# Arduino_Uno_Satyajeet.net
KiCad netlist of a schematic drawn in EAGLE
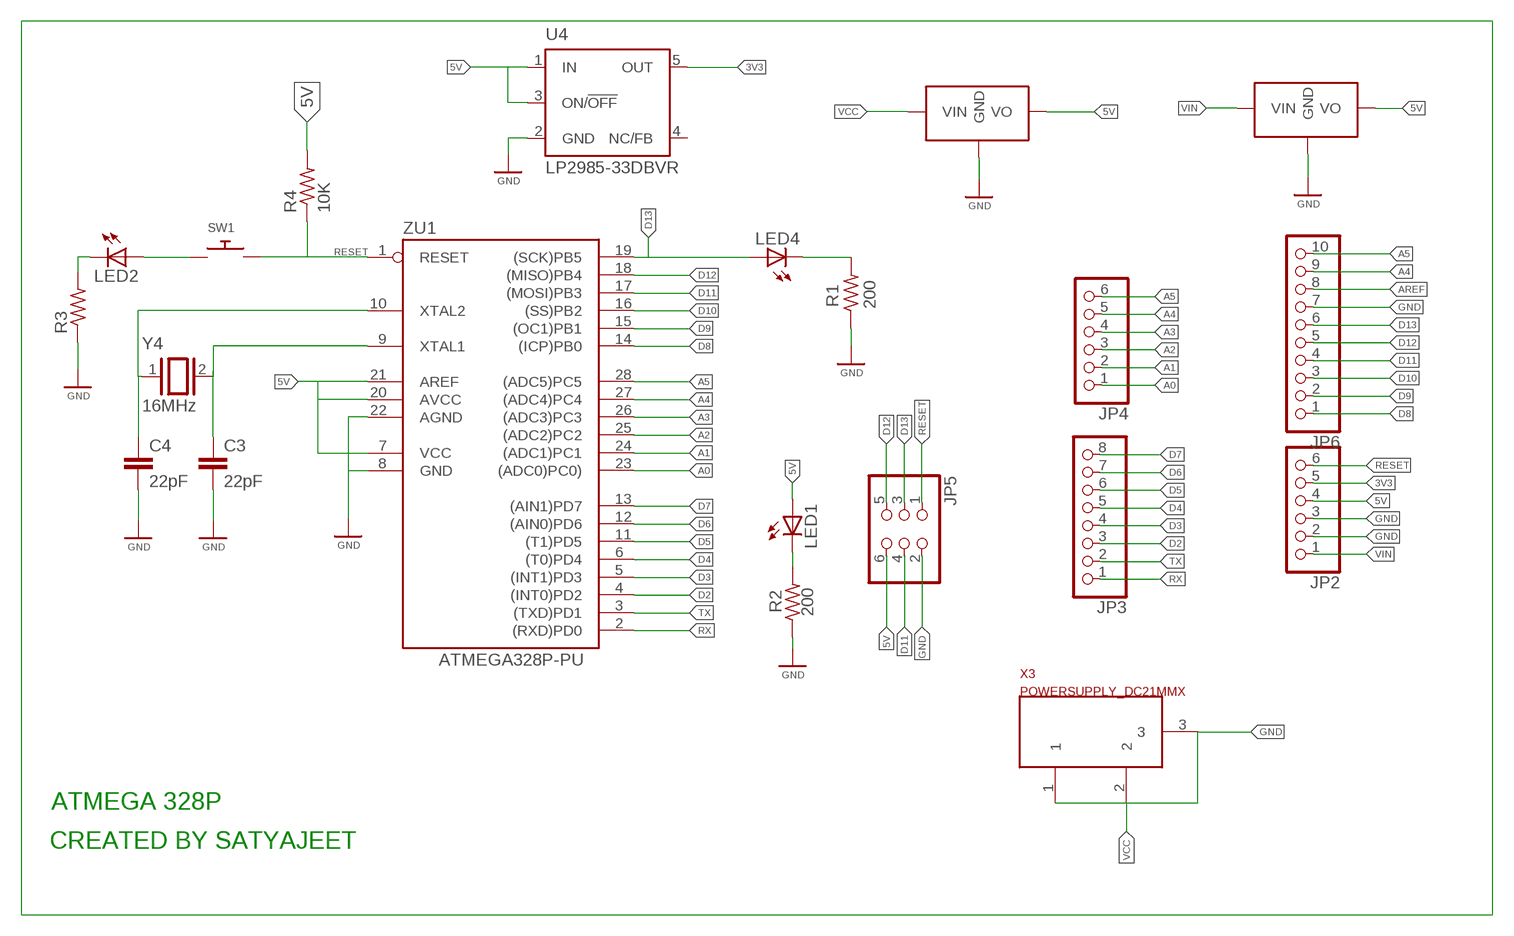
[diagram p0: schematic, sheet 1]

(export (version "E")
  (design (tool "Eeschema 10.0.6"))
  (components
    (comp (ref "C3")
      (value "22pF")
      (footprint "eagle-import:C2.5-2")
      (libsource (lib "eagle-import") (part "C2.5/2"))
    )
    (comp (ref "C4")
      (value "22pF")
      (footprint "eagle-import:C2.5-2")
      (libsource (lib "eagle-import") (part "C2.5/2"))
    )
    (comp (ref "JP2")
      (value "PINHD-1X6")
      (footprint "eagle-import:1X06")
      (libsource (lib "eagle-import") (part "PINHD-1X6"))
    )
    (comp (ref "JP3")
      (value "PINHD-1X8")
      (footprint "eagle-import:1X08")
      (libsource (lib "eagle-import") (part "PINHD-1X8"))
    )
    (comp (ref "JP4")
      (value "PINHD-1X6")
      (footprint "eagle-import:1X06")
      (libsource (lib "eagle-import") (part "PINHD-1X6"))
    )
    (comp (ref "JP5")
      (value "PINHD-2X3")
      (footprint "eagle-import:2X03")
      (libsource (lib "eagle-import") (part "PINHD-2X3"))
    )
    (comp (ref "JP6")
      (value "PINHD-1X10")
      (footprint "eagle-import:1X10")
      (libsource (lib "eagle-import") (part "PINHD-1X10"))
    )
    (comp (ref "LED1")
      (value "LED5MM")
      (footprint "eagle-import:LED5MM")
      (libsource (lib "eagle-import") (part "LED5MM"))
    )
    (comp (ref "LED2")
      (value "LED5MM")
      (footprint "eagle-import:LED5MM")
      (libsource (lib "eagle-import") (part "LED5MM"))
    )
    (comp (ref "LED4")
      (value "LED5MM")
      (footprint "eagle-import:LED5MM")
      (libsource (lib "eagle-import") (part "LED5MM"))
    )
    (comp (ref "R1")
      (value "200")
      (footprint "eagle-import:0204_5")
      (libsource (lib "eagle-import") (part "R-US_0204/5"))
    )
    (comp (ref "R2")
      (value "200")
      (footprint "eagle-import:0204_5")
      (libsource (lib "eagle-import") (part "R-US_0204/5"))
    )
    (comp (ref "R3")
      (value "R-US_0204/5")
      (footprint "eagle-import:0204_5")
      (libsource (lib "eagle-import") (part "R-US_0204/5"))
    )
    (comp (ref "R4")
      (value "10K")
      (footprint "eagle-import:0204_5")
      (libsource (lib "eagle-import") (part "R-US_0204/5"))
    )
    (comp (ref "SW1")
      (value "SWITCH_PUSHBUTTONEVQ-PE")
      (footprint "eagle-import:TACT_PANA-EVQ")
      (libsource (lib "eagle-import") (part "SWITCH_PUSHBUTTONEVQ-PE"))
    )
    (comp (ref "U$1")
      (value "AB_7805_FLAT")
      (footprint "eagle-import:AB_7805_FLAT")
      (libsource (lib "eagle-import") (part "AB_7805_FLAT"))
    )
    (comp (ref "U$2")
      (value "AB_7805_FLAT")
      (footprint "eagle-import:AB_7805_FLAT")
      (libsource (lib "eagle-import") (part "AB_7805_FLAT"))
    )
    (comp (ref "U4")
      (value "LP2985-33DBVR")
      (footprint "eagle-import:SOT23-DBV")
      (libsource (lib "eagle-import") (part "LP2985-XXDBVR33"))
    )
    (comp (ref "X3")
      (value "POWERSUPPLY_DC21MMX")
      (footprint "eagle-import:POWERSUPPLY_DC-21MM")
      (libsource (lib "eagle-import") (part "POWERSUPPLY_DC21MMX"))
    )
    (comp (ref "Y4")
      (value "16MHz")
      (footprint "eagle-import:QS")
      (libsource (lib "eagle-import") (part "XTAL/S"))
    )
    (comp (ref "ZU1")
      (value "ATMEGA328P-PU")
      (footprint "eagle-import:DIL28-3")
      (libsource (lib "eagle-import") (part "ATMEGA328P-PU"))
    )
  )
  (nets
    (net (code "1") (name "3V3") (class "Default")
      (node (ref "JP2") (pin "5") (pinfunction "5_5") (pintype "passive"))
      (node (ref "U4") (pin "5") (pinfunction "OUT_5") (pintype "passive"))
    )
    (net (code "2") (name "5V") (class "Default")
      (node (ref "JP2") (pin "4") (pinfunction "4_4") (pintype "passive"))
      (node (ref "JP5") (pin "6") (pinfunction "6_6") (pintype "passive"))
      (node (ref "LED1") (pin "A") (pinfunction "A_A") (pintype "passive"))
      (node (ref "R4") (pin "2") (pinfunction "2_2") (pintype "passive"))
      (node (ref "U$1") (pin "3") (pinfunction "VO_3") (pintype "bidirectional"))
      (node (ref "U$2") (pin "3") (pinfunction "VO_3") (pintype "bidirectional"))
      (node (ref "U4") (pin "1") (pinfunction "IN_1") (pintype "input"))
      (node (ref "ZU1") (pin "21") (pinfunction "AREF_21") (pintype "passive"))
    )
    (net (code "3") (name "A0") (class "Default")
      (node (ref "JP4") (pin "1") (pinfunction "1_1") (pintype "passive"))
      (node (ref "ZU1") (pin "23") (pinfunction "(ADC0)PC0)_23") (pintype "bidirectional"))
    )
    (net (code "4") (name "A1") (class "Default")
      (node (ref "JP4") (pin "2") (pinfunction "2_2") (pintype "passive"))
      (node (ref "ZU1") (pin "24") (pinfunction "(ADC1)PC1_24") (pintype "bidirectional"))
    )
    (net (code "5") (name "A2") (class "Default")
      (node (ref "JP4") (pin "3") (pinfunction "3_3") (pintype "passive"))
      (node (ref "ZU1") (pin "25") (pinfunction "(ADC2)PC2_25") (pintype "bidirectional"))
    )
    (net (code "6") (name "A3") (class "Default")
      (node (ref "JP4") (pin "4") (pinfunction "4_4") (pintype "passive"))
      (node (ref "ZU1") (pin "26") (pinfunction "(ADC3)PC3_26") (pintype "bidirectional"))
    )
    (net (code "7") (name "A4") (class "Default")
      (node (ref "JP4") (pin "5") (pinfunction "5_5") (pintype "passive"))
      (node (ref "JP6") (pin "9") (pinfunction "9_9") (pintype "passive"))
      (node (ref "ZU1") (pin "27") (pinfunction "(ADC4)PC4_27") (pintype "bidirectional"))
    )
    (net (code "8") (name "A5") (class "Default")
      (node (ref "JP4") (pin "6") (pinfunction "6_6") (pintype "passive"))
      (node (ref "JP6") (pin "10") (pinfunction "10_10") (pintype "passive"))
      (node (ref "ZU1") (pin "28") (pinfunction "(ADC5)PC5_28") (pintype "bidirectional"))
    )
    (net (code "9") (name "AREF") (class "Default")
      (node (ref "JP6") (pin "8") (pinfunction "8_8") (pintype "passive"))
    )
    (net (code "10") (name "D2") (class "Default")
      (node (ref "JP3") (pin "3") (pinfunction "3_3") (pintype "passive"))
      (node (ref "ZU1") (pin "4") (pinfunction "(INT0)PD2_4") (pintype "bidirectional"))
    )
    (net (code "11") (name "D3") (class "Default")
      (node (ref "JP3") (pin "4") (pinfunction "4_4") (pintype "passive"))
      (node (ref "ZU1") (pin "5") (pinfunction "(INT1)PD3_5") (pintype "bidirectional"))
    )
    (net (code "12") (name "D4") (class "Default")
      (node (ref "JP3") (pin "5") (pinfunction "5_5") (pintype "passive"))
      (node (ref "ZU1") (pin "6") (pinfunction "(T0)PD4_6") (pintype "bidirectional"))
    )
    (net (code "13") (name "D5") (class "Default")
      (node (ref "JP3") (pin "6") (pinfunction "6_6") (pintype "passive"))
      (node (ref "ZU1") (pin "11") (pinfunction "(T1)PD5_11") (pintype "bidirectional"))
    )
    (net (code "14") (name "D6") (class "Default")
      (node (ref "JP3") (pin "7") (pinfunction "7_7") (pintype "passive"))
      (node (ref "ZU1") (pin "12") (pinfunction "(AIN0)PD6_12") (pintype "bidirectional"))
    )
    (net (code "15") (name "D7") (class "Default")
      (node (ref "JP3") (pin "8") (pinfunction "8_8") (pintype "passive"))
      (node (ref "ZU1") (pin "13") (pinfunction "(AIN1)PD7_13") (pintype "bidirectional"))
    )
    (net (code "16") (name "D8") (class "Default")
      (node (ref "JP6") (pin "1") (pinfunction "1_1") (pintype "passive"))
      (node (ref "ZU1") (pin "14") (pinfunction "(ICP)PB0_14") (pintype "bidirectional"))
    )
    (net (code "17") (name "D9") (class "Default")
      (node (ref "JP6") (pin "2") (pinfunction "2_2") (pintype "passive"))
      (node (ref "ZU1") (pin "15") (pinfunction "(OC1)PB1_15") (pintype "bidirectional"))
    )
    (net (code "18") (name "D10") (class "Default")
      (node (ref "JP6") (pin "3") (pinfunction "3_3") (pintype "passive"))
      (node (ref "ZU1") (pin "16") (pinfunction "(SS)PB2_16") (pintype "bidirectional"))
    )
    (net (code "19") (name "D11") (class "Default")
      (node (ref "JP5") (pin "4") (pinfunction "4_4") (pintype "passive"))
      (node (ref "JP6") (pin "4") (pinfunction "4_4") (pintype "passive"))
      (node (ref "ZU1") (pin "17") (pinfunction "(MOSI)PB3_17") (pintype "bidirectional"))
    )
    (net (code "20") (name "D12") (class "Default")
      (node (ref "JP5") (pin "5") (pinfunction "5_5") (pintype "passive"))
      (node (ref "JP6") (pin "5") (pinfunction "5_5") (pintype "passive"))
      (node (ref "ZU1") (pin "18") (pinfunction "(MISO)PB4_18") (pintype "bidirectional"))
    )
    (net (code "21") (name "D13") (class "Default")
      (node (ref "JP5") (pin "3") (pinfunction "3_3") (pintype "passive"))
      (node (ref "JP6") (pin "6") (pinfunction "6_6") (pintype "passive"))
      (node (ref "LED4") (pin "A") (pinfunction "A_A") (pintype "passive"))
      (node (ref "ZU1") (pin "19") (pinfunction "(SCK)PB5_19") (pintype "bidirectional"))
    )
    (net (code "22") (name "GND") (class "Default")
      (node (ref "C3") (pin "2") (pinfunction "2_2") (pintype "passive"))
      (node (ref "C4") (pin "2") (pinfunction "2_2") (pintype "passive"))
      (node (ref "JP2") (pin "2") (pinfunction "2_2") (pintype "passive"))
      (node (ref "JP2") (pin "3") (pinfunction "3_3") (pintype "passive"))
      (node (ref "JP5") (pin "2") (pinfunction "2_2") (pintype "passive"))
      (node (ref "JP6") (pin "7") (pinfunction "7_7") (pintype "passive"))
      (node (ref "R1") (pin "1") (pinfunction "1_1") (pintype "passive"))
      (node (ref "R2") (pin "1") (pinfunction "1_1") (pintype "passive"))
      (node (ref "R3") (pin "1") (pinfunction "1_1") (pintype "passive"))
      (node (ref "U$1") (pin "2") (pinfunction "GND_2") (pintype "bidirectional"))
      (node (ref "U$2") (pin "2") (pinfunction "GND_2") (pintype "bidirectional"))
      (node (ref "U4") (pin "2") (pinfunction "GND_2") (pintype "power_in"))
      (node (ref "X3") (pin "1") (pinfunction "1_1") (pintype "power_in"))
      (node (ref "X3") (pin "3") (pinfunction "3_3") (pintype "power_in"))
      (node (ref "ZU1") (pin "22") (pinfunction "AGND_22") (pintype "power_in"))
    )
    (net (code "23") (name "Net-(LED1-C)") (class "Default")
      (node (ref "LED1") (pin "K") (pinfunction "C_K") (pintype "passive"))
      (node (ref "R2") (pin "2") (pinfunction "2_2") (pintype "passive"))
    )
    (net (code "24") (name "Net-(LED2-C)") (class "Default")
      (node (ref "LED2") (pin "K") (pinfunction "C_K") (pintype "passive"))
      (node (ref "R3") (pin "2") (pinfunction "2_2") (pintype "passive"))
    )
    (net (code "25") (name "Net-(LED2-PadA)") (class "Default")
      (node (ref "LED2") (pin "A") (pinfunction "A_A") (pintype "passive"))
      (node (ref "SW1") (pin "P$1") (pinfunction "P$1_P$1") (pintype "passive"))
    )
    (net (code "26") (name "Net-(LED4-C)") (class "Default")
      (node (ref "LED4") (pin "K") (pinfunction "C_K") (pintype "passive"))
      (node (ref "R1") (pin "2") (pinfunction "2_2") (pintype "passive"))
    )
    (net (code "27") (name "Net-(ZU1-XTAL1)") (class "Default")
      (node (ref "C3") (pin "1") (pinfunction "1_1") (pintype "passive"))
      (node (ref "Y4") (pin "2") (pinfunction "2_2") (pintype "passive"))
      (node (ref "ZU1") (pin "9") (pinfunction "XTAL1_9") (pintype "bidirectional"))
    )
    (net (code "28") (name "Net-(ZU1-XTAL2)") (class "Default")
      (node (ref "C4") (pin "1") (pinfunction "1_1") (pintype "passive"))
      (node (ref "Y4") (pin "1") (pinfunction "1_1") (pintype "passive"))
      (node (ref "ZU1") (pin "10") (pinfunction "XTAL2_10") (pintype "bidirectional"))
    )
    (net (code "29") (name "RESET") (class "Default")
      (node (ref "JP2") (pin "6") (pinfunction "6_6") (pintype "passive"))
      (node (ref "JP5") (pin "1") (pinfunction "1_1") (pintype "passive"))
      (node (ref "SW1") (pin "P$2") (pinfunction "P$2_P$2") (pintype "passive"))
      (node (ref "ZU1") (pin "1") (pinfunction "RESET_1") (pintype "input"))
    )
    (net (code "30") (name "RX") (class "Default")
      (node (ref "JP3") (pin "1") (pinfunction "1_1") (pintype "passive"))
      (node (ref "ZU1") (pin "2") (pinfunction "(RXD)PD0_2") (pintype "bidirectional"))
    )
    (net (code "31") (name "TX") (class "Default")
      (node (ref "JP3") (pin "2") (pinfunction "2_2") (pintype "passive"))
      (node (ref "ZU1") (pin "3") (pinfunction "(TXD)PD1_3") (pintype "bidirectional"))
    )
    (net (code "32") (name "VCC") (class "Default")
      (node (ref "U$1") (pin "1") (pinfunction "VIN_1") (pintype "bidirectional"))
      (node (ref "X3") (pin "2") (pinfunction "2_2") (pintype "power_in"))
    )
    (net (code "33") (name "VIN") (class "Default")
      (node (ref "JP2") (pin "1") (pinfunction "1_1") (pintype "passive"))
      (node (ref "U$2") (pin "1") (pinfunction "VIN_1") (pintype "bidirectional"))
    )
    (net (code "34") (name "unconnected-(R4-Pad1)") (class "Default")
      (node (ref "R4") (pin "1") (pinfunction "1_1") (pintype "passive"))
    )
    (net (code "35") (name "unconnected-(U4-NC{slash}FB-Pad4)") (class "Default")
      (node (ref "U4") (pin "4") (pinfunction "NC/FB_4") (pintype "passive"))
    )
    (net (code "36") (name "unconnected-(U4-ON{slash}~{OFF}-Pad3)") (class "Default")
      (node (ref "U4") (pin "3") (pinfunction "ON/~{OFF}_3") (pintype "input"))
    )
    (net (code "37") (name "unconnected-(ZU1-AVCC-Pad20)") (class "Default")
      (node (ref "ZU1") (pin "20") (pinfunction "AVCC_20") (pintype "power_in"))
    )
    (net (code "38") (name "unconnected-(ZU1-GND-Pad8)") (class "Default")
      (node (ref "ZU1") (pin "8") (pinfunction "GND_8") (pintype "power_in"))
    )
    (net (code "39") (name "unconnected-(ZU1-VCC-Pad7)") (class "Default")
      (node (ref "ZU1") (pin "7") (pinfunction "VCC_7") (pintype "power_in"))
    )
  )
)
